# CAN_HB_PV_Heatpump.net
KiCad netlist of a schematic drawn in EAGLE
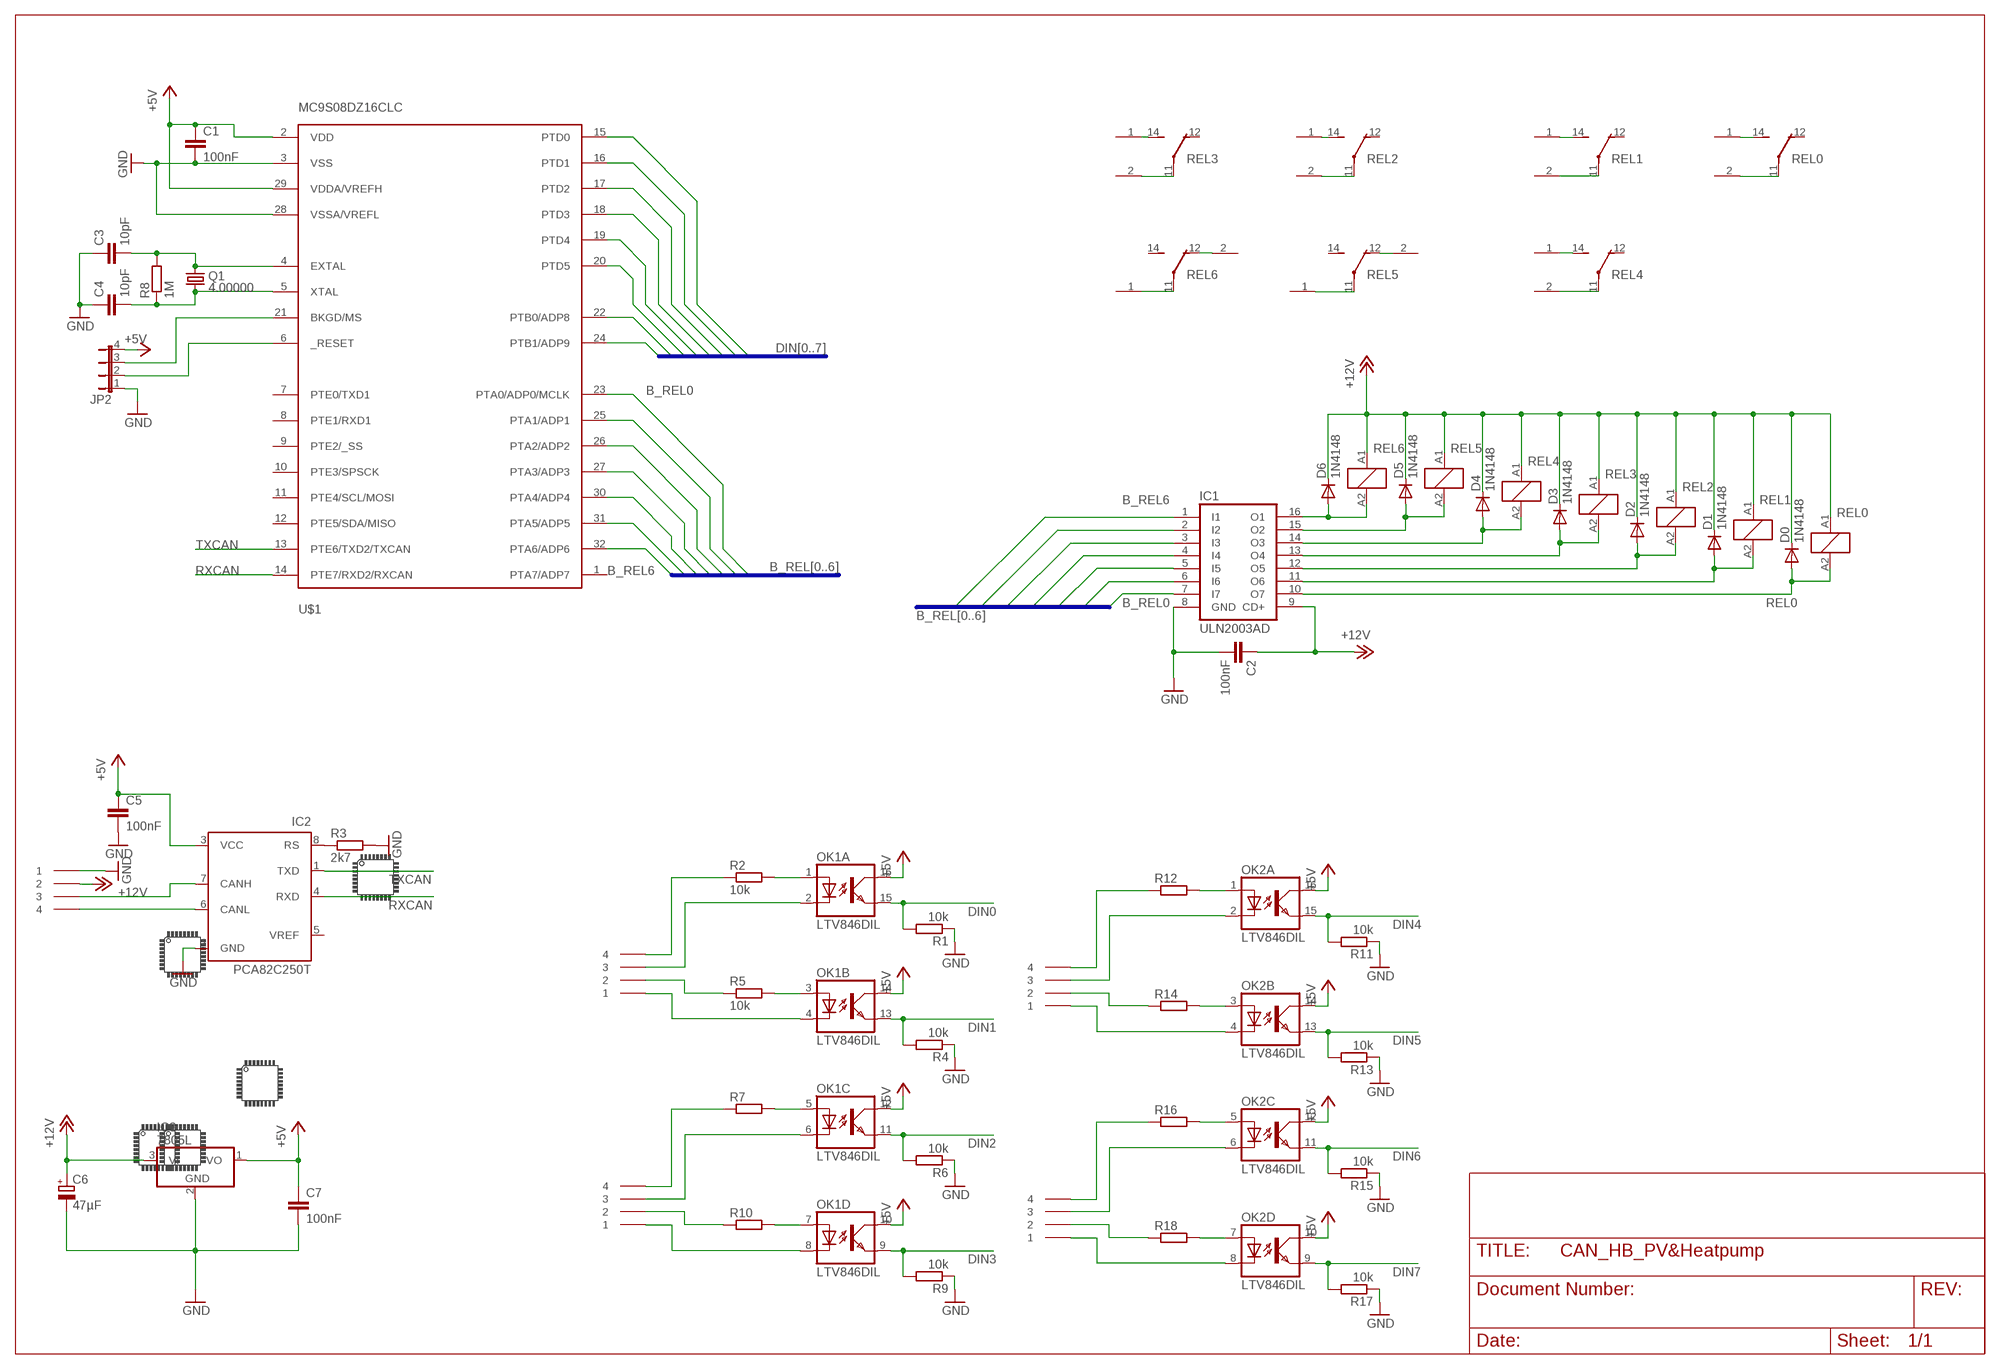
[diagram p0: schematic, sheet 1]

(export (version "E")
  (design (tool "Eeschema 10.0.6"))
  (components
    (comp (ref "C1")
      (value "100nF")
      (footprint "eagle-import:C0805K")
      (libsource (lib "eagle-import") (part "C-EUC0805K"))
    )
    (comp (ref "C2")
      (value "100nF")
      (footprint "eagle-import:C0805")
      (libsource (lib "eagle-import") (part "rcl_334_C-EUC0805"))
    )
    (comp (ref "C3")
      (value "10pF")
      (footprint "eagle-import:C0805K")
      (libsource (lib "eagle-import") (part "C-EUC0805K"))
    )
    (comp (ref "C4")
      (value "10pF")
      (footprint "eagle-import:C0805K")
      (libsource (lib "eagle-import") (part "C-EUC0805K"))
    )
    (comp (ref "C5")
      (value "100nF")
      (footprint "eagle-import:C0805")
      (libsource (lib "eagle-import") (part "C-EUC0805"))
    )
    (comp (ref "C6")
      (value "47µF")
      (footprint "eagle-import:E2-5")
      (libsource (lib "eagle-import") (part "CPOL-EUE2-5"))
    )
    (comp (ref "C7")
      (value "100nF")
      (footprint "eagle-import:C0805K")
      (libsource (lib "eagle-import") (part "C-EUC0805K"))
    )
    (comp (ref "D0")
      (value "1N4148")
      (footprint "eagle-import:SOD80C")
      (libsource (lib "eagle-import") (part "DIODE-SOD80C"))
    )
    (comp (ref "D1")
      (value "1N4148")
      (footprint "eagle-import:SOD80C")
      (libsource (lib "eagle-import") (part "DIODE-SOD80C"))
    )
    (comp (ref "D2")
      (value "1N4148")
      (footprint "eagle-import:SOD80C")
      (libsource (lib "eagle-import") (part "DIODE-SOD80C"))
    )
    (comp (ref "D3")
      (value "1N4148")
      (footprint "eagle-import:SOD80C")
      (libsource (lib "eagle-import") (part "DIODE-SOD80C"))
    )
    (comp (ref "D4")
      (value "1N4148")
      (footprint "eagle-import:SOD80C")
      (libsource (lib "eagle-import") (part "DIODE-SOD80C"))
    )
    (comp (ref "D5")
      (value "1N4148")
      (footprint "eagle-import:SOD80C")
      (libsource (lib "eagle-import") (part "DIODE-SOD80C"))
    )
    (comp (ref "D6")
      (value "1N4148")
      (footprint "eagle-import:SOD80C")
      (libsource (lib "eagle-import") (part "DIODE-SOD80C"))
    )
    (comp (ref "IC1")
      (value "ULN2003AD")
      (footprint "eagle-import:SO16")
      (libsource (lib "eagle-import") (part "ULN2003AD"))
    )
    (comp (ref "IC2")
      (value "PCA82C250T")
      (footprint "eagle-import:SO8")
      (libsource (lib "eagle-import") (part "PCA82C250T"))
    )
    (comp (ref "IC3")
      (value "7805L")
      (footprint "eagle-import:TO92")
      (libsource (lib "eagle-import") (part "78L05"))
    )
    (comp (ref "JP2")
      (value "JP4E")
      (footprint "eagle-import:JP4")
      (libsource (lib "eagle-import") (part "JP4E"))
    )
    (comp (ref "KL1")
      (value "AST021-04")
      (footprint "eagle-import:AST021-04")
      (libsource (lib "eagle-import") (part "AST021-04"))
    )
    (comp (ref "KL2")
      (value "AST021-04")
      (footprint "eagle-import:AST021-04")
      (libsource (lib "eagle-import") (part "AST021-04"))
    )
    (comp (ref "KL3")
      (value "AST021-04")
      (footprint "eagle-import:AST021-04")
      (libsource (lib "eagle-import") (part "AST021-04"))
    )
    (comp (ref "KL4")
      (value "AST021-04")
      (footprint "eagle-import:AST021-04")
      (libsource (lib "eagle-import") (part "AST021-04"))
    )
    (comp (ref "KL5")
      (value "AST021-04")
      (footprint "eagle-import:AST021-04")
      (libsource (lib "eagle-import") (part "AST021-04"))
    )
    (comp (ref "OK1")
      (value "LTV846DIL")
      (footprint "eagle-import:DIL16")
      (libsource (lib "eagle-import") (part "LTV846DIL"))
    )
    (comp (ref "OK2")
      (value "LTV846DIL")
      (footprint "eagle-import:DIL16")
      (libsource (lib "eagle-import") (part "LTV846DIL"))
    )
    (comp (ref "Q1")
      (value "4.00000")
      (footprint "eagle-import:HC49U-V")
      (libsource (lib "eagle-import") (part "CRYTALHC49U-V"))
    )
    (comp (ref "R1")
      (value "10k")
      (footprint "eagle-import:R0805")
      (libsource (lib "eagle-import") (part "rcl_334_R-EU_R0805"))
    )
    (comp (ref "R2")
      (value "10k")
      (footprint "eagle-import:R0805")
      (libsource (lib "eagle-import") (part "rcl_334_R-EU_R0805"))
    )
    (comp (ref "R3")
      (value "2k7")
      (footprint "eagle-import:R0805")
      (libsource (lib "eagle-import") (part "R-EU_R0805"))
    )
    (comp (ref "R4")
      (value "10k")
      (footprint "eagle-import:R0805")
      (libsource (lib "eagle-import") (part "rcl_334_R-EU_R0805"))
    )
    (comp (ref "R5")
      (value "10k")
      (footprint "eagle-import:R0805")
      (libsource (lib "eagle-import") (part "rcl_334_R-EU_R0805"))
    )
    (comp (ref "R6")
      (value "10k")
      (footprint "eagle-import:R0805")
      (libsource (lib "eagle-import") (part "rcl_334_R-EU_R0805"))
    )
    (comp (ref "R7")
      (value "R-EU_R0805")
      (footprint "eagle-import:R0805")
      (libsource (lib "eagle-import") (part "rcl_334_R-EU_R0805"))
    )
    (comp (ref "R8")
      (value "1M")
      (footprint "eagle-import:R0805")
      (libsource (lib "eagle-import") (part "R-EU_R0805"))
    )
    (comp (ref "R9")
      (value "10k")
      (footprint "eagle-import:R0805")
      (libsource (lib "eagle-import") (part "rcl_334_R-EU_R0805"))
    )
    (comp (ref "R10")
      (value "R-EU_R0805")
      (footprint "eagle-import:R0805")
      (libsource (lib "eagle-import") (part "rcl_334_R-EU_R0805"))
    )
    (comp (ref "R11")
      (value "10k")
      (footprint "eagle-import:R0805")
      (libsource (lib "eagle-import") (part "rcl_334_R-EU_R0805"))
    )
    (comp (ref "R12")
      (value "R-EU_R0805")
      (footprint "eagle-import:R0805")
      (libsource (lib "eagle-import") (part "rcl_334_R-EU_R0805"))
    )
    (comp (ref "R13")
      (value "10k")
      (footprint "eagle-import:R0805")
      (libsource (lib "eagle-import") (part "rcl_334_R-EU_R0805"))
    )
    (comp (ref "R14")
      (value "R-EU_R0805")
      (footprint "eagle-import:R0805")
      (libsource (lib "eagle-import") (part "rcl_334_R-EU_R0805"))
    )
    (comp (ref "R15")
      (value "10k")
      (footprint "eagle-import:R0805")
      (libsource (lib "eagle-import") (part "rcl_334_R-EU_R0805"))
    )
    (comp (ref "R16")
      (value "R-EU_R0805")
      (footprint "eagle-import:R0805")
      (libsource (lib "eagle-import") (part "rcl_334_R-EU_R0805"))
    )
    (comp (ref "R17")
      (value "10k")
      (footprint "eagle-import:R0805")
      (libsource (lib "eagle-import") (part "rcl_334_R-EU_R0805"))
    )
    (comp (ref "R18")
      (value "R-EU_R0805")
      (footprint "eagle-import:R0805")
      (libsource (lib "eagle-import") (part "rcl_334_R-EU_R0805"))
    )
    (comp (ref "REL0")
      (value "FIN34.51FIN34.51.7")
      (footprint "eagle-import:FIN34")
      (libsource (lib "eagle-import") (part "FIN34.51FIN34.51.7"))
    )
    (comp (ref "REL1")
      (value "FIN34.51FIN34.51.7")
      (footprint "eagle-import:FIN34")
      (libsource (lib "eagle-import") (part "FIN34.51FIN34.51.7"))
    )
    (comp (ref "REL2")
      (value "FIN34.51FIN34.51.7")
      (footprint "eagle-import:FIN34")
      (libsource (lib "eagle-import") (part "FIN34.51FIN34.51.7"))
    )
    (comp (ref "REL3")
      (value "FIN34.51FIN34.51.7")
      (footprint "eagle-import:FIN34")
      (libsource (lib "eagle-import") (part "FIN34.51FIN34.51.7"))
    )
    (comp (ref "REL4")
      (value "FIN34.51FIN34.51.7")
      (footprint "eagle-import:FIN34")
      (libsource (lib "eagle-import") (part "FIN34.51FIN34.51.7"))
    )
    (comp (ref "REL5")
      (value "FIN34.51FIN34.51.7")
      (footprint "eagle-import:FIN34")
      (libsource (lib "eagle-import") (part "FIN34.51FIN34.51.7"))
    )
    (comp (ref "REL6")
      (value "FIN34.51FIN34.51.7")
      (footprint "eagle-import:FIN34")
      (libsource (lib "eagle-import") (part "FIN34.51FIN34.51.7"))
    )
    (comp (ref "U$1")
      (value "MC9S08DZ16CLC")
      (footprint "eagle-import:LQFP32")
      (libsource (lib "eagle-import") (part "MC9S08DZ16CLC"))
    )
    (comp (ref "U$2")
      (value "AKL320-02")
      (footprint "eagle-import:AKL320-02")
      (libsource (lib "eagle-import") (part "AKL320-02"))
    )
    (comp (ref "U$3")
      (value "AKL320-02")
      (footprint "eagle-import:AKL320-02")
      (libsource (lib "eagle-import") (part "AKL320-02"))
    )
    (comp (ref "U$4")
      (value "AKL320-02")
      (footprint "eagle-import:AKL320-02")
      (libsource (lib "eagle-import") (part "AKL320-02"))
    )
    (comp (ref "U$5")
      (value "AKL320-02")
      (footprint "eagle-import:AKL320-02")
      (libsource (lib "eagle-import") (part "AKL320-02"))
    )
    (comp (ref "U$6")
      (value "AKL320-02")
      (footprint "eagle-import:AKL320-02")
      (libsource (lib "eagle-import") (part "AKL320-02"))
    )
    (comp (ref "U$14")
      (value "AKL320-02")
      (footprint "eagle-import:AKL320-02")
      (libsource (lib "eagle-import") (part "AKL320-02"))
    )
    (comp (ref "U$15")
      (value "AKL320-02")
      (footprint "eagle-import:AKL320-02")
      (libsource (lib "eagle-import") (part "AKL320-02"))
    )
  )
  (nets
    (net (code "1") (name "+5V") (class "Default")
      (node (ref "C1") (pin "1") (pinfunction "1_1") (pintype "passive"))
      (node (ref "C5") (pin "1") (pinfunction "1_1") (pintype "passive"))
      (node (ref "C7") (pin "1") (pinfunction "1_1") (pintype "passive"))
      (node (ref "IC2") (pin "3") (pinfunction "VCC_3") (pintype "power_in"))
      (node (ref "IC3") (pin "1") (pinfunction "VO_1") (pintype "passive"))
      (node (ref "JP2") (pin "4") (pinfunction "4_4") (pintype "passive"))
      (node (ref "OK1") (pin "10") (pinfunction "COL_10") (pintype "passive"))
      (node (ref "OK1") (pin "12") (pinfunction "COL_12") (pintype "passive"))
      (node (ref "OK1") (pin "14") (pinfunction "COL_14") (pintype "passive"))
      (node (ref "OK1") (pin "16") (pinfunction "COL_16") (pintype "passive"))
      (node (ref "OK2") (pin "10") (pinfunction "COL_10") (pintype "passive"))
      (node (ref "OK2") (pin "12") (pinfunction "COL_12") (pintype "passive"))
      (node (ref "OK2") (pin "14") (pinfunction "COL_14") (pintype "passive"))
      (node (ref "OK2") (pin "16") (pinfunction "COL_16") (pintype "passive"))
      (node (ref "U$1") (pin "2") (pinfunction "VDD_2") (pintype "power_in"))
      (node (ref "U$1") (pin "29") (pinfunction "VDDA/VREFH_29") (pintype "power_in"))
    )
    (net (code "2") (name "+12V") (class "Default")
      (node (ref "C2") (pin "1") (pinfunction "1_1") (pintype "passive"))
      (node (ref "C6") (pin "+") (pinfunction "+_+") (pintype "passive"))
      (node (ref "D0") (pin "C") (pinfunction "C_C") (pintype "passive"))
      (node (ref "D1") (pin "C") (pinfunction "C_C") (pintype "passive"))
      (node (ref "D2") (pin "C") (pinfunction "C_C") (pintype "passive"))
      (node (ref "D3") (pin "C") (pinfunction "C_C") (pintype "passive"))
      (node (ref "D4") (pin "C") (pinfunction "C_C") (pintype "passive"))
      (node (ref "D5") (pin "C") (pinfunction "C_C") (pintype "passive"))
      (node (ref "D6") (pin "C") (pinfunction "C_C") (pintype "passive"))
      (node (ref "IC1") (pin "9") (pinfunction "CD+_9") (pintype "passive"))
      (node (ref "IC3") (pin "3") (pinfunction "VI_3") (pintype "input"))
      (node (ref "KL1") (pin "P$2") (pinfunction "2_P$2") (pintype "bidirectional"))
      (node (ref "REL0") (pin "A1") (pinfunction "1_A1") (pintype "passive"))
      (node (ref "REL1") (pin "A1") (pinfunction "1_A1") (pintype "passive"))
      (node (ref "REL2") (pin "A1") (pinfunction "1_A1") (pintype "passive"))
      (node (ref "REL3") (pin "A1") (pinfunction "1_A1") (pintype "passive"))
      (node (ref "REL4") (pin "A1") (pinfunction "1_A1") (pintype "passive"))
      (node (ref "REL5") (pin "A1") (pinfunction "1_A1") (pintype "passive"))
      (node (ref "REL6") (pin "A1") (pinfunction "1_A1") (pintype "passive"))
    )
    (net (code "3") (name "/B_REL0") (class "Default")
      (node (ref "IC1") (pin "7") (pinfunction "I7_7") (pintype "input"))
      (node (ref "U$1") (pin "23") (pinfunction "PTA0/ADP0/MCLK_23") (pintype "bidirectional"))
    )
    (net (code "4") (name "/B_REL1") (class "Default")
      (node (ref "IC1") (pin "6") (pinfunction "I6_6") (pintype "input"))
      (node (ref "U$1") (pin "25") (pinfunction "PTA1/ADP1_25") (pintype "bidirectional"))
    )
    (net (code "5") (name "/B_REL2") (class "Default")
      (node (ref "IC1") (pin "5") (pinfunction "I5_5") (pintype "input"))
      (node (ref "U$1") (pin "26") (pinfunction "PTA2/ADP2_26") (pintype "bidirectional"))
    )
    (net (code "6") (name "/B_REL3") (class "Default")
      (node (ref "IC1") (pin "4") (pinfunction "I4_4") (pintype "input"))
      (node (ref "U$1") (pin "27") (pinfunction "PTA3/ADP3_27") (pintype "bidirectional"))
    )
    (net (code "7") (name "/B_REL4") (class "Default")
      (node (ref "IC1") (pin "3") (pinfunction "I3_3") (pintype "input"))
      (node (ref "U$1") (pin "30") (pinfunction "PTA4/ADP4_30") (pintype "bidirectional"))
    )
    (net (code "8") (name "/B_REL5") (class "Default")
      (node (ref "IC1") (pin "2") (pinfunction "I2_2") (pintype "input"))
      (node (ref "U$1") (pin "31") (pinfunction "PTA5/ADP5_31") (pintype "bidirectional"))
    )
    (net (code "9") (name "/B_REL6") (class "Default")
      (node (ref "IC1") (pin "1") (pinfunction "I1_1") (pintype "input"))
      (node (ref "U$1") (pin "32") (pinfunction "PTA6/ADP6_32") (pintype "bidirectional"))
    )
    (net (code "11") (name "/DIN0") (class "Default")
      (node (ref "OK1") (pin "15") (pinfunction "EMIT_15") (pintype "passive"))
      (node (ref "R1") (pin "2") (pinfunction "2_2") (pintype "passive"))
      (node (ref "U$1") (pin "15") (pinfunction "PTD0_15") (pintype "bidirectional"))
    )
    (net (code "12") (name "/DIN1") (class "Default")
      (node (ref "OK1") (pin "13") (pinfunction "EMIT_13") (pintype "passive"))
      (node (ref "R4") (pin "2") (pinfunction "2_2") (pintype "passive"))
      (node (ref "U$1") (pin "16") (pinfunction "PTD1_16") (pintype "bidirectional"))
    )
    (net (code "13") (name "/DIN2") (class "Default")
      (node (ref "OK1") (pin "11") (pinfunction "EMIT_11") (pintype "passive"))
      (node (ref "R6") (pin "2") (pinfunction "2_2") (pintype "passive"))
      (node (ref "U$1") (pin "17") (pinfunction "PTD2_17") (pintype "bidirectional"))
    )
    (net (code "14") (name "/DIN3") (class "Default")
      (node (ref "OK1") (pin "9") (pinfunction "EMIT_9") (pintype "passive"))
      (node (ref "R9") (pin "2") (pinfunction "2_2") (pintype "passive"))
      (node (ref "U$1") (pin "18") (pinfunction "PTD3_18") (pintype "bidirectional"))
    )
    (net (code "15") (name "/DIN4") (class "Default")
      (node (ref "OK2") (pin "15") (pinfunction "EMIT_15") (pintype "passive"))
      (node (ref "R11") (pin "2") (pinfunction "2_2") (pintype "passive"))
      (node (ref "U$1") (pin "19") (pinfunction "PTD4_19") (pintype "bidirectional"))
    )
    (net (code "16") (name "/DIN5") (class "Default")
      (node (ref "OK2") (pin "13") (pinfunction "EMIT_13") (pintype "passive"))
      (node (ref "R13") (pin "2") (pinfunction "2_2") (pintype "passive"))
      (node (ref "U$1") (pin "20") (pinfunction "PTD5_20") (pintype "bidirectional"))
    )
    (net (code "17") (name "/DIN6") (class "Default")
      (node (ref "OK2") (pin "11") (pinfunction "EMIT_11") (pintype "passive"))
      (node (ref "R15") (pin "2") (pinfunction "2_2") (pintype "passive"))
      (node (ref "U$1") (pin "22") (pinfunction "PTB0/ADP8_22") (pintype "bidirectional"))
    )
    (net (code "18") (name "/DIN7") (class "Default")
      (node (ref "OK2") (pin "9") (pinfunction "EMIT_9") (pintype "passive"))
      (node (ref "R17") (pin "2") (pinfunction "2_2") (pintype "passive"))
      (node (ref "U$1") (pin "24") (pinfunction "PTB1/ADP9_24") (pintype "bidirectional"))
    )
    (net (code "20") (name "/REL0") (class "Default")
      (node (ref "D0") (pin "A") (pinfunction "A_A") (pintype "passive"))
      (node (ref "IC1") (pin "10") (pinfunction "O7_10") (pintype "open_collector"))
      (node (ref "REL0") (pin "A2") (pinfunction "2_A2") (pintype "passive"))
    )
    (net (code "21") (name "/RXCAN") (class "Default")
      (node (ref "IC2") (pin "4") (pinfunction "RXD_4") (pintype "output"))
      (node (ref "U$1") (pin "14") (pinfunction "PTE7/RXD2/RXCAN_14") (pintype "input"))
    )
    (net (code "22") (name "/TXCAN") (class "Default")
      (node (ref "IC2") (pin "1") (pinfunction "TXD_1") (pintype "input"))
      (node (ref "U$1") (pin "13") (pinfunction "PTE6/TXD2/TXCAN_13") (pintype "output"))
    )
    (net (code "23") (name "GND") (class "Default")
      (node (ref "C1") (pin "2") (pinfunction "2_2") (pintype "passive"))
      (node (ref "C2") (pin "2") (pinfunction "2_2") (pintype "passive"))
      (node (ref "C3") (pin "1") (pinfunction "1_1") (pintype "passive"))
      (node (ref "C4") (pin "1") (pinfunction "1_1") (pintype "passive"))
      (node (ref "C5") (pin "2") (pinfunction "2_2") (pintype "passive"))
      (node (ref "C6") (pin "-") (pinfunction "-_-") (pintype "passive"))
      (node (ref "C7") (pin "2") (pinfunction "2_2") (pintype "passive"))
      (node (ref "IC1") (pin "8") (pinfunction "GND_8") (pintype "power_in"))
      (node (ref "IC2") (pin "2") (pinfunction "GND_2") (pintype "power_in"))
      (node (ref "IC3") (pin "2") (pinfunction "GND_2") (pintype "passive"))
      (node (ref "JP2") (pin "1") (pinfunction "1_1") (pintype "passive"))
      (node (ref "KL1") (pin "P$1") (pinfunction "1_P$1") (pintype "bidirectional"))
      (node (ref "R1") (pin "1") (pinfunction "1_1") (pintype "passive"))
      (node (ref "R11") (pin "1") (pinfunction "1_1") (pintype "passive"))
      (node (ref "R13") (pin "1") (pinfunction "1_1") (pintype "passive"))
      (node (ref "R15") (pin "1") (pinfunction "1_1") (pintype "passive"))
      (node (ref "R17") (pin "1") (pinfunction "1_1") (pintype "passive"))
      (node (ref "R3") (pin "2") (pinfunction "2_2") (pintype "passive"))
      (node (ref "R4") (pin "1") (pinfunction "1_1") (pintype "passive"))
      (node (ref "R6") (pin "1") (pinfunction "1_1") (pintype "passive"))
      (node (ref "R9") (pin "1") (pinfunction "1_1") (pintype "passive"))
      (node (ref "U$1") (pin "28") (pinfunction "VSSA/VREFL_28") (pintype "power_in"))
      (node (ref "U$1") (pin "3") (pinfunction "VSS_3") (pintype "power_in"))
    )
    (net (code "24") (name "Net-(IC1-O1)") (class "Default")
      (node (ref "D6") (pin "A") (pinfunction "A_A") (pintype "passive"))
      (node (ref "IC1") (pin "16") (pinfunction "O1_16") (pintype "open_collector"))
      (node (ref "REL6") (pin "A2") (pinfunction "2_A2") (pintype "passive"))
    )
    (net (code "25") (name "Net-(IC1-O2)") (class "Default")
      (node (ref "D5") (pin "A") (pinfunction "A_A") (pintype "passive"))
      (node (ref "IC1") (pin "15") (pinfunction "O2_15") (pintype "open_collector"))
      (node (ref "REL5") (pin "A2") (pinfunction "2_A2") (pintype "passive"))
    )
    (net (code "26") (name "Net-(IC1-O3)") (class "Default")
      (node (ref "D4") (pin "A") (pinfunction "A_A") (pintype "passive"))
      (node (ref "IC1") (pin "14") (pinfunction "O3_14") (pintype "open_collector"))
      (node (ref "REL4") (pin "A2") (pinfunction "2_A2") (pintype "passive"))
    )
    (net (code "27") (name "Net-(IC1-O4)") (class "Default")
      (node (ref "D3") (pin "A") (pinfunction "A_A") (pintype "passive"))
      (node (ref "IC1") (pin "13") (pinfunction "O4_13") (pintype "open_collector"))
      (node (ref "REL3") (pin "A2") (pinfunction "2_A2") (pintype "passive"))
    )
    (net (code "28") (name "Net-(IC1-O5)") (class "Default")
      (node (ref "D2") (pin "A") (pinfunction "A_A") (pintype "passive"))
      (node (ref "IC1") (pin "12") (pinfunction "O5_12") (pintype "open_collector"))
      (node (ref "REL2") (pin "A2") (pinfunction "2_A2") (pintype "passive"))
    )
    (net (code "29") (name "Net-(IC1-O6)") (class "Default")
      (node (ref "D1") (pin "A") (pinfunction "A_A") (pintype "passive"))
      (node (ref "IC1") (pin "11") (pinfunction "O6_11") (pintype "open_collector"))
      (node (ref "REL1") (pin "A2") (pinfunction "2_A2") (pintype "passive"))
    )
    (net (code "30") (name "Net-(IC2-CANH)") (class "Default")
      (node (ref "IC2") (pin "7") (pinfunction "CANH_7") (pintype "bidirectional"))
      (node (ref "KL1") (pin "P$3") (pinfunction "3_P$3") (pintype "bidirectional"))
    )
    (net (code "31") (name "Net-(IC2-CANL)") (class "Default")
      (node (ref "IC2") (pin "6") (pinfunction "CANL_6") (pintype "bidirectional"))
      (node (ref "KL1") (pin "P$4") (pinfunction "4_P$4") (pintype "bidirectional"))
    )
    (net (code "32") (name "Net-(IC2-RS)") (class "Default")
      (node (ref "IC2") (pin "8") (pinfunction "RS_8") (pintype "input"))
      (node (ref "R3") (pin "1") (pinfunction "1_1") (pintype "passive"))
    )
    (net (code "33") (name "Net-(KL2-1)") (class "Default")
      (node (ref "KL2") (pin "P$1") (pinfunction "1_P$1") (pintype "bidirectional"))
      (node (ref "OK1") (pin "4") (pinfunction "C_4") (pintype "passive"))
    )
    (net (code "34") (name "Net-(KL2-2)") (class "Default")
      (node (ref "KL2") (pin "P$2") (pinfunction "2_P$2") (pintype "bidirectional"))
      (node (ref "R5") (pin "1") (pinfunction "1_1") (pintype "passive"))
    )
    (net (code "35") (name "Net-(KL2-3)") (class "Default")
      (node (ref "KL2") (pin "P$3") (pinfunction "3_P$3") (pintype "bidirectional"))
      (node (ref "OK1") (pin "2") (pinfunction "C_2") (pintype "passive"))
    )
    (net (code "36") (name "Net-(KL2-4)") (class "Default")
      (node (ref "KL2") (pin "P$4") (pinfunction "4_P$4") (pintype "bidirectional"))
      (node (ref "R2") (pin "1") (pinfunction "1_1") (pintype "passive"))
    )
    (net (code "37") (name "Net-(KL3-1)") (class "Default")
      (node (ref "KL3") (pin "P$1") (pinfunction "1_P$1") (pintype "bidirectional"))
      (node (ref "OK1") (pin "8") (pinfunction "C_8") (pintype "passive"))
    )
    (net (code "38") (name "Net-(KL3-2)") (class "Default")
      (node (ref "KL3") (pin "P$2") (pinfunction "2_P$2") (pintype "bidirectional"))
      (node (ref "R10") (pin "1") (pinfunction "1_1") (pintype "passive"))
    )
    (net (code "39") (name "Net-(KL3-3)") (class "Default")
      (node (ref "KL3") (pin "P$3") (pinfunction "3_P$3") (pintype "bidirectional"))
      (node (ref "OK1") (pin "6") (pinfunction "C_6") (pintype "passive"))
    )
    (net (code "40") (name "Net-(KL3-4)") (class "Default")
      (node (ref "KL3") (pin "P$4") (pinfunction "4_P$4") (pintype "bidirectional"))
      (node (ref "R7") (pin "1") (pinfunction "1_1") (pintype "passive"))
    )
    (net (code "41") (name "Net-(KL4-1)") (class "Default")
      (node (ref "KL4") (pin "P$1") (pinfunction "1_P$1") (pintype "bidirectional"))
      (node (ref "OK2") (pin "4") (pinfunction "C_4") (pintype "passive"))
    )
    (net (code "42") (name "Net-(KL4-2)") (class "Default")
      (node (ref "KL4") (pin "P$2") (pinfunction "2_P$2") (pintype "bidirectional"))
      (node (ref "R14") (pin "1") (pinfunction "1_1") (pintype "passive"))
    )
    (net (code "43") (name "Net-(KL4-3)") (class "Default")
      (node (ref "KL4") (pin "P$3") (pinfunction "3_P$3") (pintype "bidirectional"))
      (node (ref "OK2") (pin "2") (pinfunction "C_2") (pintype "passive"))
    )
    (net (code "44") (name "Net-(KL4-4)") (class "Default")
      (node (ref "KL4") (pin "P$4") (pinfunction "4_P$4") (pintype "bidirectional"))
      (node (ref "R12") (pin "1") (pinfunction "1_1") (pintype "passive"))
    )
    (net (code "45") (name "Net-(KL5-1)") (class "Default")
      (node (ref "KL5") (pin "P$1") (pinfunction "1_P$1") (pintype "bidirectional"))
      (node (ref "OK2") (pin "8") (pinfunction "C_8") (pintype "passive"))
    )
    (net (code "46") (name "Net-(KL5-2)") (class "Default")
      (node (ref "KL5") (pin "P$2") (pinfunction "2_P$2") (pintype "bidirectional"))
      (node (ref "R18") (pin "1") (pinfunction "1_1") (pintype "passive"))
    )
    (net (code "47") (name "Net-(KL5-3)") (class "Default")
      (node (ref "KL5") (pin "P$3") (pinfunction "3_P$3") (pintype "bidirectional"))
      (node (ref "OK2") (pin "6") (pinfunction "C_6") (pintype "passive"))
    )
    (net (code "48") (name "Net-(KL5-4)") (class "Default")
      (node (ref "KL5") (pin "P$4") (pinfunction "4_P$4") (pintype "bidirectional"))
      (node (ref "R16") (pin "1") (pinfunction "1_1") (pintype "passive"))
    )
    (net (code "49") (name "Net-(OK1A-A)") (class "Default")
      (node (ref "OK1") (pin "1") (pinfunction "A_1") (pintype "passive"))
      (node (ref "R2") (pin "2") (pinfunction "2_2") (pintype "passive"))
    )
    (net (code "50") (name "Net-(OK1B-A)") (class "Default")
      (node (ref "OK1") (pin "3") (pinfunction "A_3") (pintype "passive"))
      (node (ref "R5") (pin "2") (pinfunction "2_2") (pintype "passive"))
    )
    (net (code "51") (name "Net-(OK1C-A)") (class "Default")
      (node (ref "OK1") (pin "5") (pinfunction "A_5") (pintype "passive"))
      (node (ref "R7") (pin "2") (pinfunction "2_2") (pintype "passive"))
    )
    (net (code "52") (name "Net-(OK1D-A)") (class "Default")
      (node (ref "OK1") (pin "7") (pinfunction "A_7") (pintype "passive"))
      (node (ref "R10") (pin "2") (pinfunction "2_2") (pintype "passive"))
    )
    (net (code "53") (name "Net-(OK2A-A)") (class "Default")
      (node (ref "OK2") (pin "1") (pinfunction "A_1") (pintype "passive"))
      (node (ref "R12") (pin "2") (pinfunction "2_2") (pintype "passive"))
    )
    (net (code "54") (name "Net-(OK2B-A)") (class "Default")
      (node (ref "OK2") (pin "3") (pinfunction "A_3") (pintype "passive"))
      (node (ref "R14") (pin "2") (pinfunction "2_2") (pintype "passive"))
    )
    (net (code "55") (name "Net-(OK2C-A)") (class "Default")
      (node (ref "OK2") (pin "5") (pinfunction "A_5") (pintype "passive"))
      (node (ref "R16") (pin "2") (pinfunction "2_2") (pintype "passive"))
    )
    (net (code "56") (name "Net-(OK2D-A)") (class "Default")
      (node (ref "OK2") (pin "7") (pinfunction "A_7") (pintype "passive"))
      (node (ref "R18") (pin "2") (pinfunction "2_2") (pintype "passive"))
    )
    (net (code "57") (name "Net-(REL0B-P)") (class "Default")
      (node (ref "REL0") (pin "11") (pinfunction "P_11") (pintype "passive"))
      (node (ref "U$15") (pin "2") (pinfunction "P$1_2") (pintype "bidirectional"))
    )
    (net (code "58") (name "Net-(REL0B-S)") (class "Default")
      (node (ref "REL0") (pin "14") (pinfunction "S_14") (pintype "passive"))
      (node (ref "U$15") (pin "1") (pinfunction "P$1_1") (pintype "bidirectional"))
    )
    (net (code "59") (name "Net-(REL1B-P)") (class "Default")
      (node (ref "REL1") (pin "11") (pinfunction "P_11") (pintype "passive"))
      (node (ref "U$6") (pin "2") (pinfunction "P$1_2") (pintype "bidirectional"))
    )
    (net (code "60") (name "Net-(REL1B-S)") (class "Default")
      (node (ref "REL1") (pin "14") (pinfunction "S_14") (pintype "passive"))
      (node (ref "U$6") (pin "1") (pinfunction "P$1_1") (pintype "bidirectional"))
    )
    (net (code "61") (name "Net-(REL2B-P)") (class "Default")
      (node (ref "REL2") (pin "11") (pinfunction "P_11") (pintype "passive"))
      (node (ref "U$4") (pin "2") (pinfunction "P$1_2") (pintype "bidirectional"))
    )
    (net (code "62") (name "Net-(REL2B-S)") (class "Default")
      (node (ref "REL2") (pin "14") (pinfunction "S_14") (pintype "passive"))
      (node (ref "U$4") (pin "1") (pinfunction "P$1_1") (pintype "bidirectional"))
    )
    (net (code "63") (name "Net-(REL3B-P)") (class "Default")
      (node (ref "REL3") (pin "11") (pinfunction "P_11") (pintype "passive"))
      (node (ref "U$2") (pin "2") (pinfunction "P$1_2") (pintype "bidirectional"))
    )
    (net (code "64") (name "Net-(REL3B-S)") (class "Default")
      (node (ref "REL3") (pin "14") (pinfunction "S_14") (pintype "passive"))
      (node (ref "U$2") (pin "1") (pinfunction "P$1_1") (pintype "bidirectional"))
    )
    (net (code "65") (name "Net-(REL4B-P)") (class "Default")
      (node (ref "REL4") (pin "11") (pinfunction "P_11") (pintype "passive"))
      (node (ref "U$14") (pin "2") (pinfunction "P$1_2") (pintype "bidirectional"))
    )
    (net (code "66") (name "Net-(REL4B-S)") (class "Default")
      (node (ref "REL4") (pin "14") (pinfunction "S_14") (pintype "passive"))
      (node (ref "U$14") (pin "1") (pinfunction "P$1_1") (pintype "bidirectional"))
    )
    (net (code "67") (name "Net-(REL5B-O)") (class "Default")
      (node (ref "REL5") (pin "12") (pinfunction "O_12") (pintype "passive"))
      (node (ref "U$5") (pin "2") (pinfunction "P$1_2") (pintype "bidirectional"))
    )
    (net (code "68") (name "Net-(REL5B-P)") (class "Default")
      (node (ref "REL5") (pin "11") (pinfunction "P_11") (pintype "passive"))
      (node (ref "U$5") (pin "1") (pinfunction "P$1_1") (pintype "bidirectional"))
    )
    (net (code "69") (name "Net-(REL6B-O)") (class "Default")
      (node (ref "REL6") (pin "12") (pinfunction "O_12") (pintype "passive"))
      (node (ref "U$3") (pin "2") (pinfunction "P$1_2") (pintype "bidirectional"))
    )
    (net (code "70") (name "Net-(REL6B-P)") (class "Default")
      (node (ref "REL6") (pin "11") (pinfunction "P_11") (pintype "passive"))
      (node (ref "U$3") (pin "1") (pinfunction "P$1_1") (pintype "bidirectional"))
    )
    (net (code "71") (name "Net-(U$1-BKGD{slash}MS)") (class "Default")
      (node (ref "JP2") (pin "3") (pinfunction "3_3") (pintype "passive"))
      (node (ref "U$1") (pin "21") (pinfunction "BKGD/MS_21") (pintype "bidirectional"))
    )
    (net (code "72") (name "Net-(U$1-EXTAL)") (class "Default")
      (node (ref "C3") (pin "2") (pinfunction "2_2") (pintype "passive"))
      (node (ref "Q1") (pin "2") (pinfunction "2_2") (pintype "passive"))
      (node (ref "R8") (pin "2") (pinfunction "2_2") (pintype "passive"))
      (node (ref "U$1") (pin "4") (pinfunction "EXTAL_4") (pintype "bidirectional"))
    )
    (net (code "73") (name "Net-(U$1-XTAL)") (class "Default")
      (node (ref "C4") (pin "2") (pinfunction "2_2") (pintype "passive"))
      (node (ref "Q1") (pin "1") (pinfunction "1_1") (pintype "passive"))
      (node (ref "R8") (pin "1") (pinfunction "1_1") (pintype "passive"))
      (node (ref "U$1") (pin "5") (pinfunction "XTAL_5") (pintype "bidirectional"))
    )
    (net (code "74") (name "Net-(U$1-_RESET)") (class "Default")
      (node (ref "JP2") (pin "2") (pinfunction "2_2") (pintype "passive"))
      (node (ref "U$1") (pin "6") (pinfunction "_RESET_6") (pintype "bidirectional"))
    )
    (net (code "75") (name "unconnected-(IC2-VREF-Pad5)") (class "Default")
      (node (ref "IC2") (pin "5") (pinfunction "VREF_5") (pintype "output"))
    )
    (net (code "76") (name "unconnected-(REL0B-O-Pad12)") (class "Default")
      (node (ref "REL0") (pin "12") (pinfunction "O_12") (pintype "passive"))
    )
    (net (code "77") (name "unconnected-(REL1B-O-Pad12)") (class "Default")
      (node (ref "REL1") (pin "12") (pinfunction "O_12") (pintype "passive"))
    )
    (net (code "78") (name "unconnected-(REL2B-O-Pad12)") (class "Default")
      (node (ref "REL2") (pin "12") (pinfunction "O_12") (pintype "passive"))
    )
    (net (code "79") (name "unconnected-(REL3B-O-Pad12)") (class "Default")
      (node (ref "REL3") (pin "12") (pinfunction "O_12") (pintype "passive"))
    )
    (net (code "80") (name "unconnected-(REL4B-O-Pad12)") (class "Default")
      (node (ref "REL4") (pin "12") (pinfunction "O_12") (pintype "passive"))
    )
    (net (code "81") (name "unconnected-(REL5B-S-Pad14)") (class "Default")
      (node (ref "REL5") (pin "14") (pinfunction "S_14") (pintype "passive"))
    )
    (net (code "82") (name "unconnected-(REL6B-S-Pad14)") (class "Default")
      (node (ref "REL6") (pin "14") (pinfunction "S_14") (pintype "passive"))
    )
    (net (code "83") (name "unconnected-(U$1-PTA7{slash}ADP7-Pad1)") (class "Default")
      (node (ref "U$1") (pin "1") (pinfunction "PTA7/ADP7_1") (pintype "bidirectional"))
    )
    (net (code "84") (name "unconnected-(U$1-PTE0{slash}TXD1-Pad7)") (class "Default")
      (node (ref "U$1") (pin "7") (pinfunction "PTE0/TXD1_7") (pintype "bidirectional"))
    )
    (net (code "85") (name "unconnected-(U$1-PTE1{slash}RXD1-Pad8)") (class "Default")
      (node (ref "U$1") (pin "8") (pinfunction "PTE1/RXD1_8") (pintype "bidirectional"))
    )
    (net (code "86") (name "unconnected-(U$1-PTE2{slash}_SS-Pad9)") (class "Default")
      (node (ref "U$1") (pin "9") (pinfunction "PTE2/_SS_9") (pintype "bidirectional"))
    )
    (net (code "87") (name "unconnected-(U$1-PTE3{slash}SPSCK-Pad10)") (class "Default")
      (node (ref "U$1") (pin "10") (pinfunction "PTE3/SPSCK_10") (pintype "bidirectional"))
    )
    (net (code "88") (name "unconnected-(U$1-PTE4{slash}SCL{slash}MOSI-Pad11)") (class "Default")
      (node (ref "U$1") (pin "11") (pinfunction "PTE4/SCL/MOSI_11") (pintype "bidirectional"))
    )
    (net (code "89") (name "unconnected-(U$1-PTE5{slash}SDA{slash}MISO-Pad12)") (class "Default")
      (node (ref "U$1") (pin "12") (pinfunction "PTE5/SDA/MISO_12") (pintype "bidirectional"))
    )
  )
)
